# power.net
KiCad netlist of a schematic drawn in Altium Designer
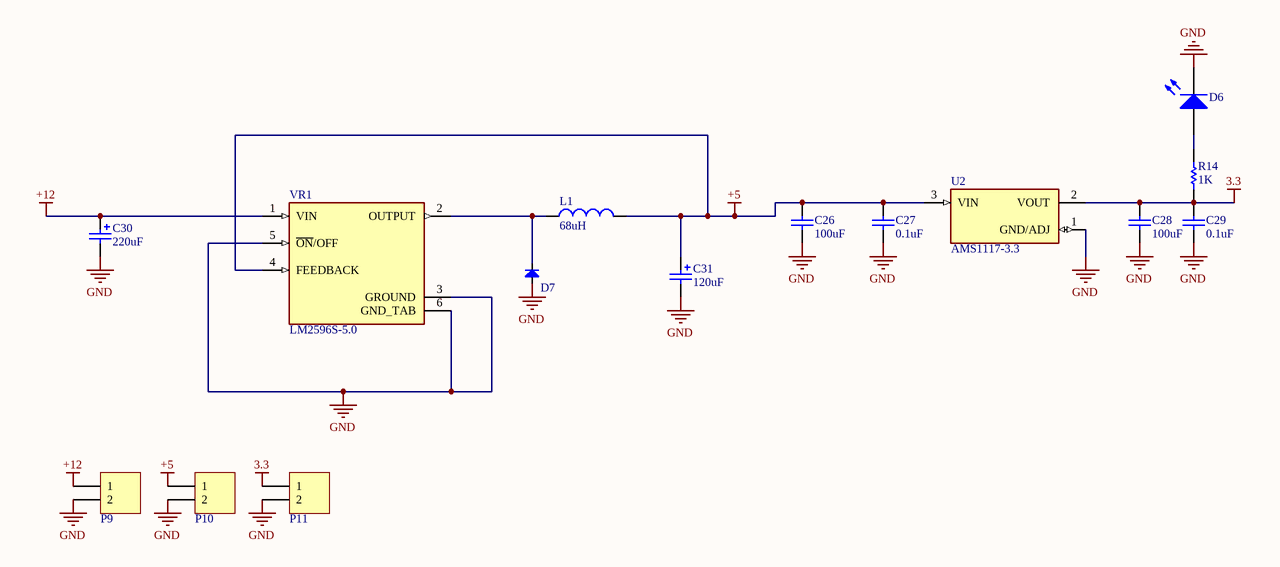
[diagram p0: power.SchDoc]

(export (version "E")
  (design (tool "Eeschema 10.0.6"))
  (components
    (comp (ref "C26")
      (value "100uF")
      (footprint "CAP-SM-0603")
      (description "Capacitor")
      (fields (field (name "Comment") "Cap Non-Pol SMD"))
      (libsource (lib "PIF_Library") (part "Cap Non-Pol SMD"))
    )
    (comp (ref "C27")
      (value "0.1uF")
      (footprint "CAP-SM-0603")
      (description "Capacitor")
      (fields (field (name "Comment") "Cap Non-Pol SMD"))
      (libsource (lib "PIF_Library") (part "Cap Non-Pol SMD"))
    )
    (comp (ref "C28")
      (value "100uF")
      (footprint "CAP-SM-0603")
      (description "Capacitor")
      (fields (field (name "Comment") "Cap Non-Pol SMD"))
      (libsource (lib "PIF_Library") (part "Cap Non-Pol SMD"))
    )
    (comp (ref "C29")
      (value "0.1uF")
      (footprint "CAP-SM-0603")
      (description "Capacitor")
      (fields (field (name "Comment") "Cap Non-Pol SMD"))
      (libsource (lib "PIF_Library") (part "Cap Non-Pol SMD"))
    )
    (comp (ref "C30")
      (value "220uF")
      (footprint "CP1.5/3.4")
      (description "Polarized Capacitor (Radial)")
      (fields (field (name "Comment") "Cap Pol"))
      (libsource (lib "PIF_Library") (part "Cap Pol"))
    )
    (comp (ref "C31")
      (value "120uF")
      (footprint "CP1.5/3.4")
      (description "Polarized Capacitor (Radial)")
      (fields (field (name "Comment") "Cap Pol"))
      (libsource (lib "PIF_Library") (part "Cap Pol"))
    )
    (comp (ref "D6")
      (value "LED SMD")
      (footprint "LED_0603_Blue")
      (description "LED")
      (libsource (lib "PIF_Library") (part "LED SMD"))
    )
    (comp (ref "D7")
      (value "Diode")
      (footprint "DIO-1A")
      (description "Default Diode")
      (fields (field (name "PUBLISHER") "Altium Limited"))
      (libsource (lib "TechMT.VN_Lib_Project v2") (part "Diode"))
    )
    (comp (ref "L1")
      (value "68uH")
      (footprint "INDUCTOR 12.5x12.5")
      (description "Inductor")
      (libsource (lib "PIF_Library") (part "Inductor"))
    )
    (comp (ref "P9")
      (value "Domino 2")
      (footprint "DOMINO 2- 5mm")
      (description "Domino, 2-Pin")
      (fields (field (name "PUBLISHER") "Altium Limited"))
      (libsource (lib "PIF_Library") (part "Domino 2"))
    )
    (comp (ref "P10")
      (value "Header 2")
      (footprint "JP2")
      (description "Header, 2-Pin")
      (fields (field (name "PUBLISHER") "Altium Limited"))
      (libsource (lib "PIF_Library") (part "Header 2"))
    )
    (comp (ref "P11")
      (value "Header 2")
      (footprint "JP2")
      (description "Header, 2-Pin")
      (fields (field (name "PUBLISHER") "Altium Limited"))
      (libsource (lib "PIF_Library") (part "Header 2"))
    )
    (comp (ref "R14")
      (value "1K")
      (footprint "RES-SM-0603")
      (description "Resistor")
      (fields (field (name "Comment") "RESISTOR SMD"))
      (libsource (lib "PIF_Library") (part "RESISTOR SMD"))
    )
    (comp (ref "U2")
      (value "AMS1117-3.3")
      (footprint "SOT229P700X180-4N")
      (description "Sot223/Pkg 1-Amp 3.3-Volt Low Drop Out Voltage Regulatator")
      (fields (field (name "MF") "Advanced Monolithic Systems"))
      (libsource (lib "AMS1117-3.3") (part "AMS1117-3.3"))
    )
    (comp (ref "VR1")
      (value "LM2596S-5.0")
      (footprint "TO170P1524X483-6N")
      (description "SIMPLE SWITCHER&reg; 4.5V to 40V, 3A Low Component Count Step-Down Regulator")
      (fields (field (name "MP") "LM2596S-5.0/NOPB") (field (name "MF") "Texas Instruments"))
      (libsource (lib "LM2596S-5.0") (part "LM2596S-5.0"))
    )
  )
  (nets
    (net (code "1") (name "+5") (class "Default")
      (node (ref "C26") (pin "2") (pinfunction "2_2") (pintype "passive"))
      (node (ref "C27") (pin "2") (pinfunction "2_2") (pintype "passive"))
      (node (ref "C31") (pin "1") (pinfunction "1_1") (pintype "passive"))
      (node (ref "L1") (pin "2") (pinfunction "2_2") (pintype "passive"))
      (node (ref "P10") (pin "1") (pinfunction "1_1") (pintype "passive"))
      (node (ref "U2") (pin "3") (pinfunction "VIN_3") (pintype "input"))
      (node (ref "VR1") (pin "4") (pinfunction "FEEDBACK_4") (pintype "input"))
    )
    (net (code "2") (name "+12") (class "Default")
      (node (ref "C30") (pin "1") (pinfunction "1_1") (pintype "passive"))
      (node (ref "P9") (pin "1") (pinfunction "1_1") (pintype "passive"))
      (node (ref "VR1") (pin "1") (pinfunction "VIN_1") (pintype "input"))
    )
    (net (code "3") (name "3.3") (class "Default")
      (node (ref "C28") (pin "2") (pinfunction "2_2") (pintype "passive"))
      (node (ref "C29") (pin "1") (pinfunction "1_1") (pintype "passive"))
      (node (ref "P11") (pin "1") (pinfunction "1_1") (pintype "passive"))
      (node (ref "R14") (pin "2") (pinfunction "2_2") (pintype "passive"))
      (node (ref "U2") (pin "2") (pinfunction "VOUT_2") (pintype "power_in"))
    )
    (net (code "4") (name "GND") (class "Default")
      (node (ref "C26") (pin "1") (pinfunction "1_1") (pintype "passive"))
      (node (ref "C27") (pin "1") (pinfunction "1_1") (pintype "passive"))
      (node (ref "C28") (pin "1") (pinfunction "1_1") (pintype "passive"))
      (node (ref "C29") (pin "2") (pinfunction "2_2") (pintype "passive"))
      (node (ref "C30") (pin "2") (pinfunction "2_2") (pintype "passive"))
      (node (ref "C31") (pin "2") (pinfunction "2_2") (pintype "passive"))
      (node (ref "D6") (pin "2") (pinfunction "K_2") (pintype "passive"))
      (node (ref "D7") (pin "1") (pinfunction "A_1") (pintype "passive"))
      (node (ref "P10") (pin "2") (pinfunction "2_2") (pintype "passive"))
      (node (ref "P11") (pin "2") (pinfunction "2_2") (pintype "passive"))
      (node (ref "P9") (pin "2") (pinfunction "2_2") (pintype "passive"))
      (node (ref "U2") (pin "1") (pinfunction "GND/ADJ_1") (pintype "bidirectional"))
      (node (ref "VR1") (pin "3") (pinfunction "GROUND_3") (pintype "power_in"))
      (node (ref "VR1") (pin "5") (pinfunction "~{ON}/OFF_5") (pintype "input"))
      (node (ref "VR1") (pin "6") (pinfunction "GND_TAB_6") (pintype "power_in"))
    )
    (net (code "5") (name "Net-(D6-A)") (class "Default")
      (node (ref "D6") (pin "1") (pinfunction "A_1") (pintype "passive"))
      (node (ref "R14") (pin "1") (pinfunction "1_1") (pintype "passive"))
    )
    (net (code "6") (name "Net-(D7-K)") (class "Default")
      (node (ref "D7") (pin "2") (pinfunction "K_2") (pintype "passive"))
      (node (ref "L1") (pin "1") (pinfunction "1_1") (pintype "passive"))
      (node (ref "VR1") (pin "2") (pinfunction "OUTPUT_2") (pintype "output"))
    )
  )
)
